# Banks_3_4.net
KiCad netlist of a schematic drawn in Altium Designer
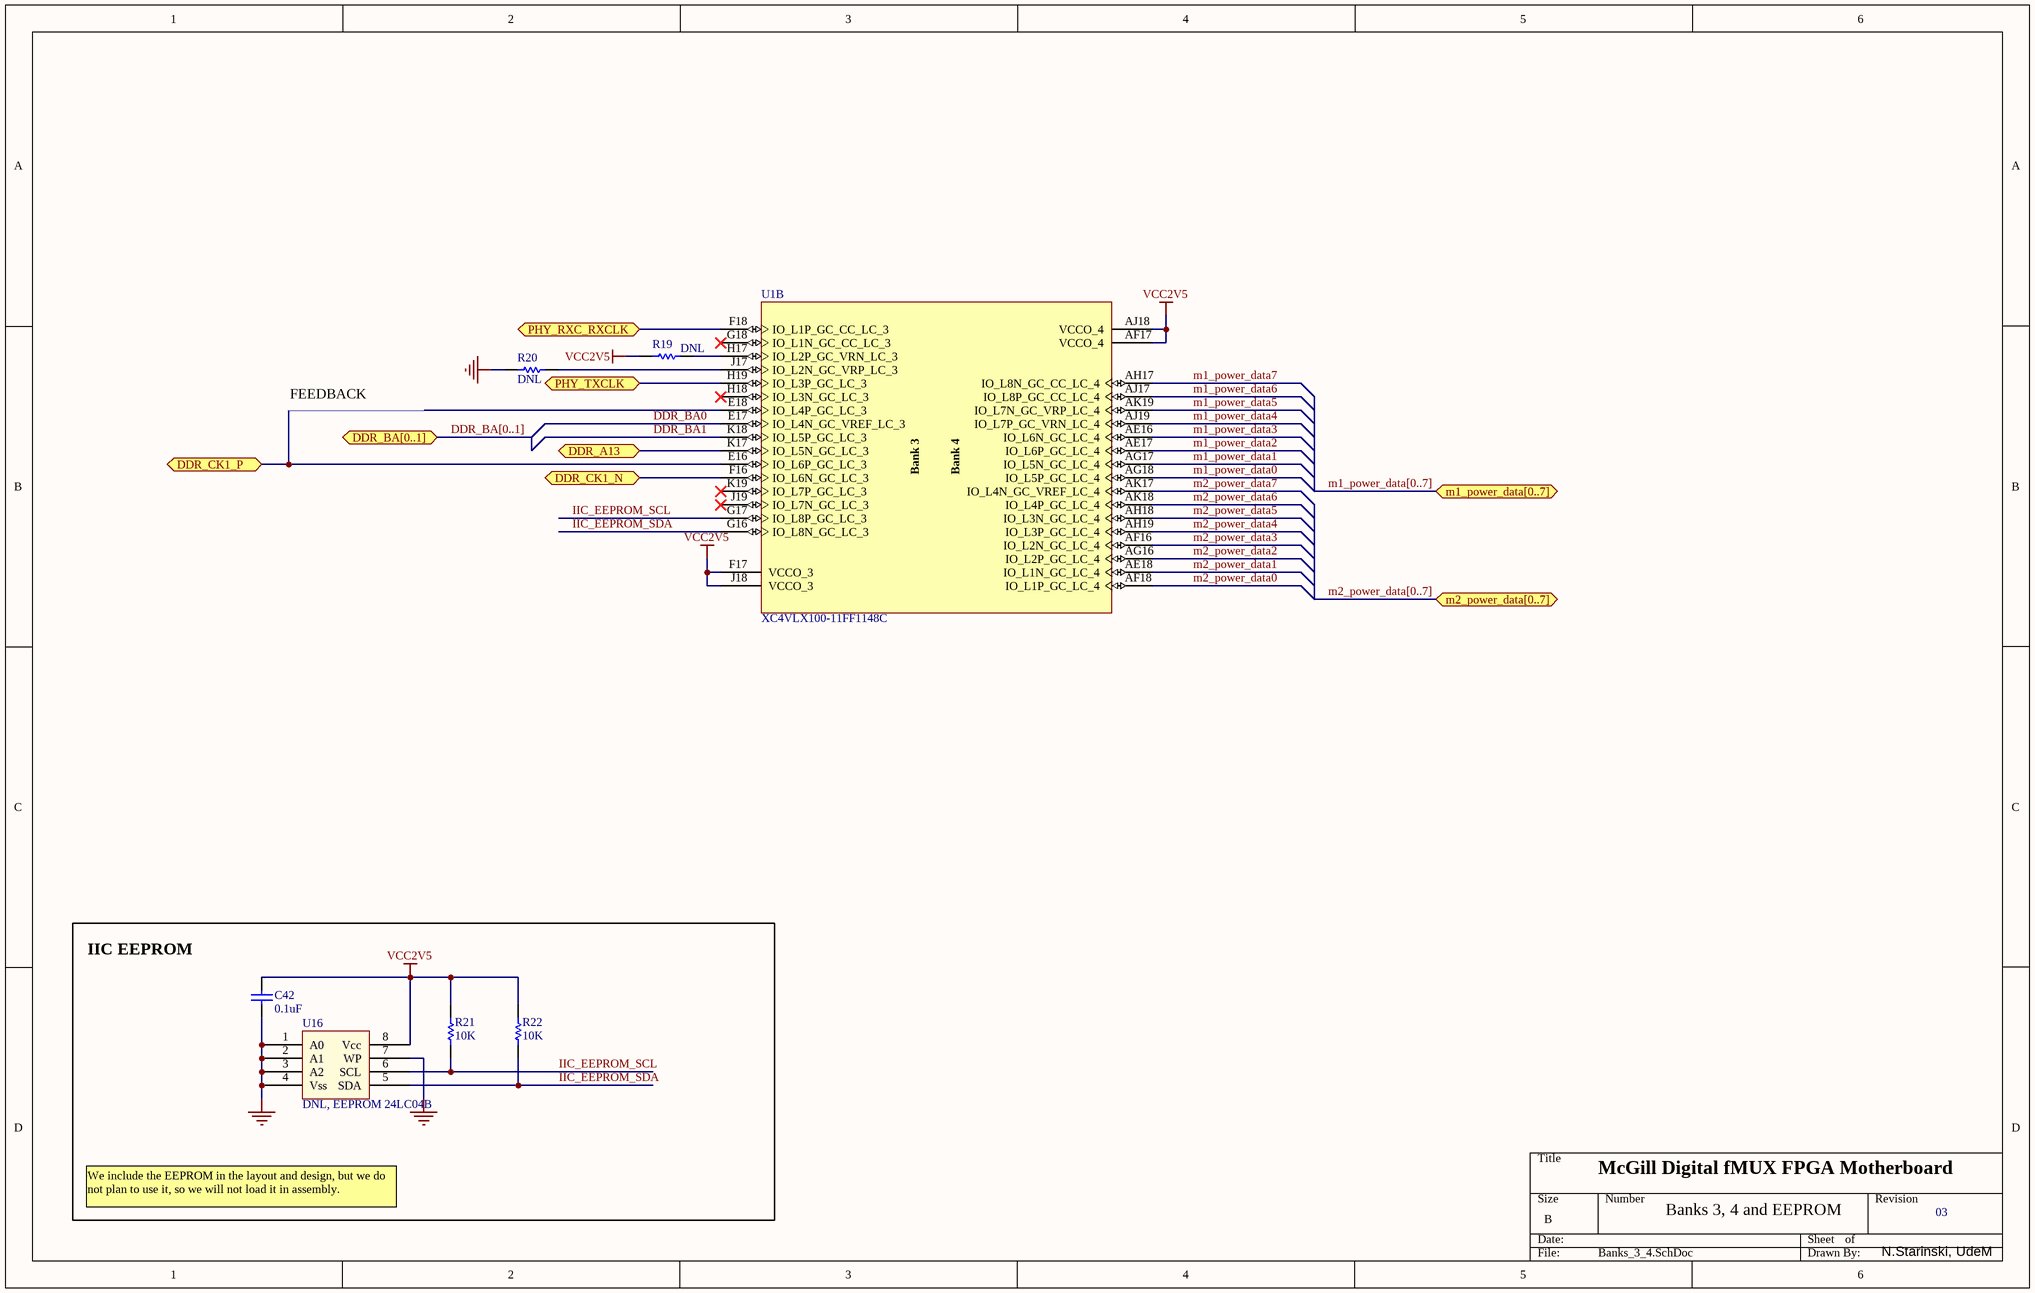
[diagram p0: Banks_3_4.SchDoc]

(export (version "E")
  (design (tool "Eeschema 10.0.6"))
  (components
    (comp (ref "C42")
      (value "0.1uF")
      (footprint "CC1608-0603")
      (description "Capacitor (Semiconductor SIM Model)")
      (fields (field (name "PUBLISHER") "Altium Limited"))
      (libsource (lib "Miscellaneous Devices") (part "Cap Semi"))
    )
    (comp (ref "R19")
      (value "DNL")
      (footprint "CR1608-0603")
      (description "Semiconductor Resistor")
      (fields (field (name "PUBLISHER") "Altium Limited"))
      (libsource (lib "Miscellaneous Devices") (part "Res Semi"))
    )
    (comp (ref "R20")
      (value "DNL")
      (footprint "CR1608-0603")
      (description "Semiconductor Resistor")
      (fields (field (name "PUBLISHER") "Altium Limited"))
      (libsource (lib "Miscellaneous Devices") (part "Res Semi"))
    )
    (comp (ref "R21")
      (value "10K")
      (footprint "CR1608-0603")
      (description "Resistor 0603")
      (fields (field (name "PUBLISHER") "Altium Limited"))
      (libsource (lib "Miscellaneous Devices") (part "Res Semi"))
    )
    (comp (ref "R22")
      (value "10K")
      (footprint "CR1608-0603")
      (description "Resistor 0603")
      (fields (field (name "PUBLISHER") "Altium Limited"))
      (libsource (lib "Miscellaneous Devices") (part "Res Semi"))
    )
    (comp (ref "U1")
      (value "XC4VLX100-11FF1148C")
      (footprint "FF1148")
      (description "Xilinx Virtex-4 LX Platform FPGA, 1148-Ball FFBGA, Speed Grade 11, 768 User I/Os, Commercial Grade")
      (fields (field (name "PUBLISHER") "Altium Limited"))
      (libsource (lib "Xilinx Virtex-4") (part "XC4VLX100-11FF1148C"))
    )
    (comp (ref "U16")
      (value "DNL, EEPROM 24LC04B")
      (footprint "TSSOP8-4.4")
      (description "4K I2C Serial EEPROM")
      (libsource (lib "I2C_Serial_EEPROM") (part "24AA04/24LC04B"))
    )
  )
  (nets
    (net (code "1") (name "/DDR_A13") (class "Default")
      (node (ref "U1") (pin "K17") (pinfunction "IO_L5N_GC_LC_3_K17") (pintype "bidirectional"))
    )
    (net (code "2") (name "/DDR_BA0") (class "Default")
      (node (ref "U1") (pin "E17") (pinfunction "IO_L4N_GC_VREF_LC_3_E17") (pintype "bidirectional"))
    )
    (net (code "3") (name "/DDR_BA1") (class "Default")
      (node (ref "U1") (pin "K18") (pinfunction "IO_L5P_GC_LC_3_K18") (pintype "bidirectional"))
    )
    (net (code "5") (name "/DDR_CK1_N") (class "Default")
      (node (ref "U1") (pin "F16") (pinfunction "IO_L6N_GC_LC_3_F16") (pintype "bidirectional"))
    )
    (net (code "6") (name "/DDR_CK1_P") (class "Default")
      (node (ref "U1") (pin "E16") (pinfunction "IO_L6P_GC_LC_3_E16") (pintype "bidirectional"))
      (node (ref "U1") (pin "E18") (pinfunction "IO_L4P_GC_LC_3_E18") (pintype "bidirectional"))
    )
    (net (code "7") (name "/IIC_EEPROM_SCL") (class "Default")
      (node (ref "R21") (pin "1") (pinfunction "1_1") (pintype "passive"))
      (node (ref "U1") (pin "G17") (pinfunction "IO_L8P_GC_LC_3_G17") (pintype "bidirectional"))
      (node (ref "U16") (pin "6") (pinfunction "SCL_6") (pintype "passive"))
    )
    (net (code "8") (name "/IIC_EEPROM_SDA") (class "Default")
      (node (ref "R22") (pin "1") (pinfunction "1_1") (pintype "passive"))
      (node (ref "U1") (pin "G16") (pinfunction "IO_L8N_GC_LC_3_G16") (pintype "bidirectional"))
      (node (ref "U16") (pin "5") (pinfunction "SDA_5") (pintype "passive"))
    )
    (net (code "9") (name "/PHY_RXC_RXCLK") (class "Default")
      (node (ref "U1") (pin "F18") (pinfunction "IO_L1P_GC_CC_LC_3_F18") (pintype "bidirectional"))
    )
    (net (code "10") (name "/PHY_TXCLK") (class "Default")
      (node (ref "U1") (pin "H19") (pinfunction "IO_L3P_GC_LC_3_H19") (pintype "bidirectional"))
    )
    (net (code "11") (name "/m1_power_data0") (class "Default")
      (node (ref "U1") (pin "AG18") (pinfunction "IO_L5P_GC_LC_4_AG18") (pintype "bidirectional"))
    )
    (net (code "12") (name "/m1_power_data1") (class "Default")
      (node (ref "U1") (pin "AG17") (pinfunction "IO_L5N_GC_LC_4_AG17") (pintype "bidirectional"))
    )
    (net (code "13") (name "/m1_power_data2") (class "Default")
      (node (ref "U1") (pin "AE17") (pinfunction "IO_L6P_GC_LC_4_AE17") (pintype "bidirectional"))
    )
    (net (code "14") (name "/m1_power_data3") (class "Default")
      (node (ref "U1") (pin "AE16") (pinfunction "IO_L6N_GC_LC_4_AE16") (pintype "bidirectional"))
    )
    (net (code "15") (name "/m1_power_data4") (class "Default")
      (node (ref "U1") (pin "AJ19") (pinfunction "IO_L7P_GC_VRN_LC_4_AJ19") (pintype "bidirectional"))
    )
    (net (code "16") (name "/m1_power_data5") (class "Default")
      (node (ref "U1") (pin "AK19") (pinfunction "IO_L7N_GC_VRP_LC_4_AK19") (pintype "bidirectional"))
    )
    (net (code "17") (name "/m1_power_data6") (class "Default")
      (node (ref "U1") (pin "AJ17") (pinfunction "IO_L8P_GC_CC_LC_4_AJ17") (pintype "bidirectional"))
    )
    (net (code "18") (name "/m1_power_data7") (class "Default")
      (node (ref "U1") (pin "AH17") (pinfunction "IO_L8N_GC_CC_LC_4_AH17") (pintype "bidirectional"))
    )
    (net (code "20") (name "/m2_power_data0") (class "Default")
      (node (ref "U1") (pin "AF18") (pinfunction "IO_L1P_GC_LC_4_AF18") (pintype "bidirectional"))
    )
    (net (code "21") (name "/m2_power_data1") (class "Default")
      (node (ref "U1") (pin "AE18") (pinfunction "IO_L1N_GC_LC_4_AE18") (pintype "bidirectional"))
    )
    (net (code "22") (name "/m2_power_data2") (class "Default")
      (node (ref "U1") (pin "AG16") (pinfunction "IO_L2P_GC_LC_4_AG16") (pintype "bidirectional"))
    )
    (net (code "23") (name "/m2_power_data3") (class "Default")
      (node (ref "U1") (pin "AF16") (pinfunction "IO_L2N_GC_LC_4_AF16") (pintype "bidirectional"))
    )
    (net (code "24") (name "/m2_power_data4") (class "Default")
      (node (ref "U1") (pin "AH19") (pinfunction "IO_L3P_GC_LC_4_AH19") (pintype "bidirectional"))
    )
    (net (code "25") (name "/m2_power_data5") (class "Default")
      (node (ref "U1") (pin "AH18") (pinfunction "IO_L3N_GC_LC_4_AH18") (pintype "bidirectional"))
    )
    (net (code "26") (name "/m2_power_data6") (class "Default")
      (node (ref "U1") (pin "AK18") (pinfunction "IO_L4P_GC_LC_4_AK18") (pintype "bidirectional"))
    )
    (net (code "27") (name "/m2_power_data7") (class "Default")
      (node (ref "U1") (pin "AK17") (pinfunction "IO_L4N_GC_VREF_LC_4_AK17") (pintype "bidirectional"))
    )
    (net (code "29") (name "GND") (class "Default")
      (node (ref "C42") (pin "1") (pinfunction "1_1") (pintype "passive"))
      (node (ref "R20") (pin "1") (pinfunction "1_1") (pintype "passive"))
      (node (ref "U16") (pin "1") (pinfunction "A0_1") (pintype "passive"))
      (node (ref "U16") (pin "2") (pinfunction "A1_2") (pintype "passive"))
      (node (ref "U16") (pin "3") (pinfunction "A2_3") (pintype "passive"))
      (node (ref "U16") (pin "4") (pinfunction "Vss_4") (pintype "power_in"))
      (node (ref "U16") (pin "7") (pinfunction "WP_7") (pintype "passive"))
    )
    (net (code "30") (name "Net-(U1B-IO_L2N_GC_VRP_LC_3)") (class "Default")
      (node (ref "R20") (pin "2") (pinfunction "2_2") (pintype "passive"))
      (node (ref "U1") (pin "J17") (pinfunction "IO_L2N_GC_VRP_LC_3_J17") (pintype "bidirectional"))
    )
    (net (code "31") (name "Net-(U1B-IO_L2P_GC_VRN_LC_3)") (class "Default")
      (node (ref "R19") (pin "2") (pinfunction "2_2") (pintype "passive"))
      (node (ref "U1") (pin "H17") (pinfunction "IO_L2P_GC_VRN_LC_3_H17") (pintype "bidirectional"))
    )
    (net (code "32") (name "VCC2V5") (class "Default")
      (node (ref "C42") (pin "2") (pinfunction "2_2") (pintype "passive"))
      (node (ref "R19") (pin "1") (pinfunction "1_1") (pintype "passive"))
      (node (ref "R21") (pin "2") (pinfunction "2_2") (pintype "passive"))
      (node (ref "R22") (pin "2") (pinfunction "2_2") (pintype "passive"))
      (node (ref "U1") (pin "AF17") (pinfunction "VCCO_4_AF17") (pintype "power_in"))
      (node (ref "U1") (pin "AJ18") (pinfunction "VCCO_4_AJ18") (pintype "power_in"))
      (node (ref "U1") (pin "F17") (pinfunction "VCCO_3_F17") (pintype "power_in"))
      (node (ref "U1") (pin "J18") (pinfunction "VCCO_3_J18") (pintype "power_in"))
      (node (ref "U16") (pin "8") (pinfunction "Vcc_8") (pintype "power_in"))
    )
    (net (code "33") (name "unconnected-(U1B-IO_L1N_GC_CC_LC_3-PadG18)") (class "Default")
      (node (ref "U1") (pin "G18") (pinfunction "IO_L1N_GC_CC_LC_3_G18") (pintype "bidirectional+no_connect"))
    )
    (net (code "34") (name "unconnected-(U1B-IO_L3N_GC_LC_3-PadH18)") (class "Default")
      (node (ref "U1") (pin "H18") (pinfunction "IO_L3N_GC_LC_3_H18") (pintype "bidirectional+no_connect"))
    )
    (net (code "35") (name "unconnected-(U1B-IO_L7N_GC_LC_3-PadJ19)") (class "Default")
      (node (ref "U1") (pin "J19") (pinfunction "IO_L7N_GC_LC_3_J19") (pintype "bidirectional+no_connect"))
    )
    (net (code "36") (name "unconnected-(U1B-IO_L7P_GC_LC_3-PadK19)") (class "Default")
      (node (ref "U1") (pin "K19") (pinfunction "IO_L7P_GC_LC_3_K19") (pintype "bidirectional+no_connect"))
    )
  )
)
